# Buttons.net
KiCad netlist of a schematic drawn in EAGLE
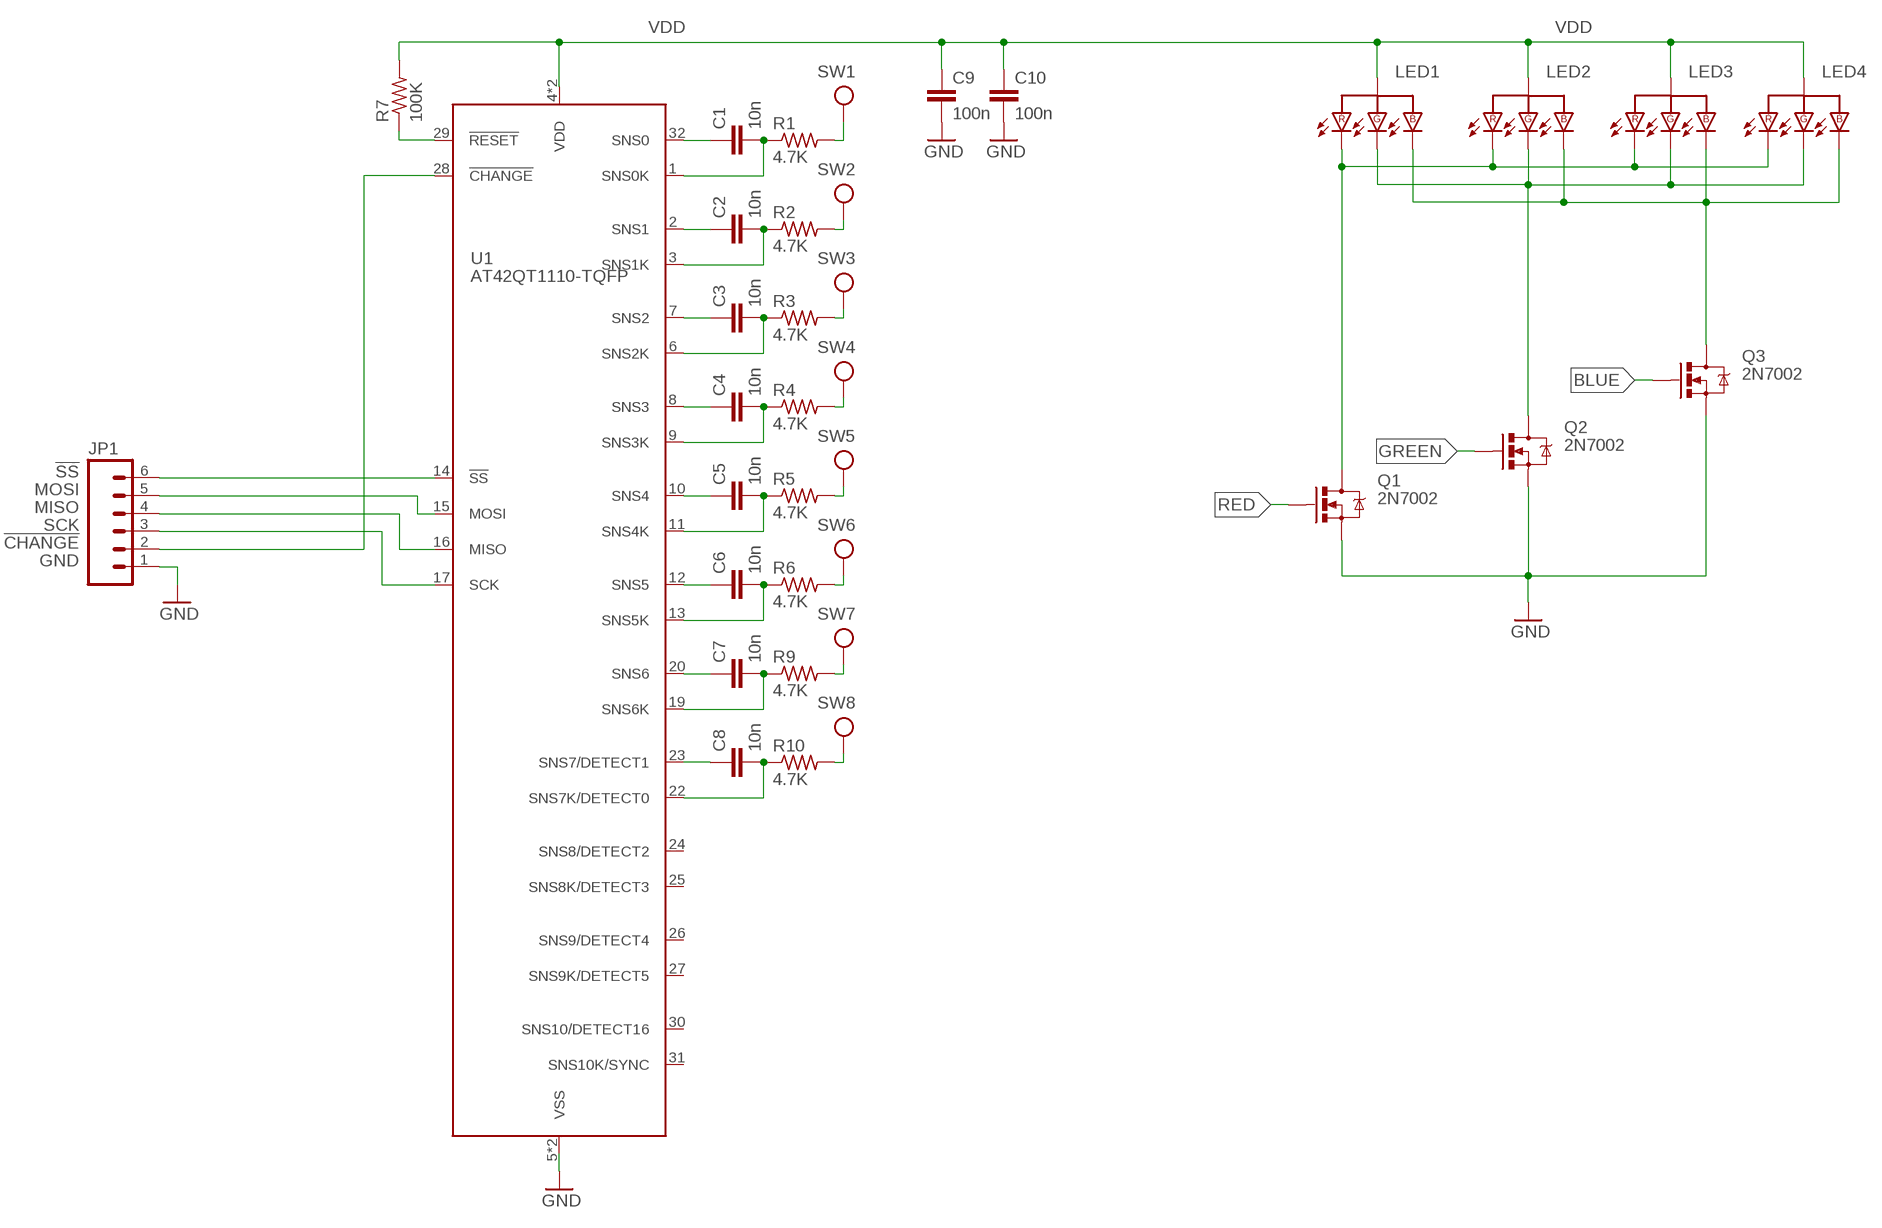
[diagram p0: schematic, sheet 1]

(export (version "E")
  (design (tool "Eeschema 10.0.6"))
  (components
    (comp (ref "C1")
      (value "10n")
      (footprint "eagle-import:C0603")
      (libsource (lib "eagle-import") (part "C-EUC0603"))
    )
    (comp (ref "C2")
      (value "10n")
      (footprint "eagle-import:C0603")
      (libsource (lib "eagle-import") (part "C-EUC0603"))
    )
    (comp (ref "C3")
      (value "10n")
      (footprint "eagle-import:C0603")
      (libsource (lib "eagle-import") (part "C-EUC0603"))
    )
    (comp (ref "C4")
      (value "10n")
      (footprint "eagle-import:C0603")
      (libsource (lib "eagle-import") (part "C-EUC0603"))
    )
    (comp (ref "C5")
      (value "10n")
      (footprint "eagle-import:C0603")
      (libsource (lib "eagle-import") (part "C-EUC0603"))
    )
    (comp (ref "C6")
      (value "10n")
      (footprint "eagle-import:C0603")
      (libsource (lib "eagle-import") (part "C-EUC0603"))
    )
    (comp (ref "C7")
      (value "10n")
      (footprint "eagle-import:C0603")
      (libsource (lib "eagle-import") (part "C-EUC0603"))
    )
    (comp (ref "C8")
      (value "10n")
      (footprint "eagle-import:C0603")
      (libsource (lib "eagle-import") (part "C-EUC0603"))
    )
    (comp (ref "C9")
      (value "100n")
      (footprint "eagle-import:C0603")
      (libsource (lib "eagle-import") (part "C-EUC0603"))
    )
    (comp (ref "C10")
      (value "100n")
      (footprint "eagle-import:C0603")
      (libsource (lib "eagle-import") (part "C-EUC0603"))
    )
    (comp (ref "JP1")
      (value "M06SMD-STRAIGHT")
      (footprint "eagle-import:1X06_SMD_STRAIGHT")
      (libsource (lib "eagle-import") (part "M06SMD-STRAIGHT"))
    )
    (comp (ref "LED1")
      (value "LED_RGB")
      (footprint "eagle-import:PLCC-4")
      (libsource (lib "eagle-import") (part "LED_RGB"))
    )
    (comp (ref "LED2")
      (value "LED_RGB")
      (footprint "eagle-import:PLCC-4")
      (libsource (lib "eagle-import") (part "LED_RGB"))
    )
    (comp (ref "LED3")
      (value "LED_RGB")
      (footprint "eagle-import:PLCC-4")
      (libsource (lib "eagle-import") (part "LED_RGB"))
    )
    (comp (ref "LED4")
      (value "LED_RGB")
      (footprint "eagle-import:PLCC-4")
      (libsource (lib "eagle-import") (part "LED_RGB"))
    )
    (comp (ref "Q1")
      (value "2N7002")
      (footprint "eagle-import:SOT23-3")
      (libsource (lib "eagle-import") (part "MOSFET-NCHANNELSMD"))
    )
    (comp (ref "Q2")
      (value "2N7002")
      (footprint "eagle-import:SOT23-3")
      (libsource (lib "eagle-import") (part "MOSFET-NCHANNELSMD"))
    )
    (comp (ref "Q3")
      (value "2N7002")
      (footprint "eagle-import:SOT23-3")
      (libsource (lib "eagle-import") (part "MOSFET-NCHANNELSMD"))
    )
    (comp (ref "R1")
      (value "4.7K")
      (footprint "eagle-import:R0603")
      (libsource (lib "eagle-import") (part "R-US_R0603"))
    )
    (comp (ref "R2")
      (value "4.7K")
      (footprint "eagle-import:R0603")
      (libsource (lib "eagle-import") (part "R-US_R0603"))
    )
    (comp (ref "R3")
      (value "4.7K")
      (footprint "eagle-import:R0603")
      (libsource (lib "eagle-import") (part "R-US_R0603"))
    )
    (comp (ref "R4")
      (value "4.7K")
      (footprint "eagle-import:R0603")
      (libsource (lib "eagle-import") (part "R-US_R0603"))
    )
    (comp (ref "R5")
      (value "4.7K")
      (footprint "eagle-import:R0603")
      (libsource (lib "eagle-import") (part "R-US_R0603"))
    )
    (comp (ref "R6")
      (value "4.7K")
      (footprint "eagle-import:R0603")
      (libsource (lib "eagle-import") (part "R-US_R0603"))
    )
    (comp (ref "R7")
      (value "100K")
      (footprint "eagle-import:R0603")
      (libsource (lib "eagle-import") (part "R-US_R0603"))
    )
    (comp (ref "R9")
      (value "4.7K")
      (footprint "eagle-import:R0603")
      (libsource (lib "eagle-import") (part "R-US_R0603"))
    )
    (comp (ref "R10")
      (value "4.7K")
      (footprint "eagle-import:R0603")
      (libsource (lib "eagle-import") (part "R-US_R0603"))
    )
    (comp (ref "SW1")
      (value "TOUCH_PAD-CIRCLE-15MM")
      (footprint "eagle-import:TOUCH-CIRCLE-15MM")
      (libsource (lib "eagle-import") (part "TOUCH_PAD-CIRCLE-15MM"))
    )
    (comp (ref "SW2")
      (value "TOUCH_PAD-CIRCLE-15MM")
      (footprint "eagle-import:TOUCH-CIRCLE-15MM")
      (libsource (lib "eagle-import") (part "TOUCH_PAD-CIRCLE-15MM"))
    )
    (comp (ref "SW3")
      (value "TOUCH_PAD-CIRCLE-15MM")
      (footprint "eagle-import:TOUCH-CIRCLE-15MM")
      (libsource (lib "eagle-import") (part "TOUCH_PAD-CIRCLE-15MM"))
    )
    (comp (ref "SW4")
      (value "TOUCH_PAD-CIRCLE-15MM")
      (footprint "eagle-import:TOUCH-CIRCLE-15MM")
      (libsource (lib "eagle-import") (part "TOUCH_PAD-CIRCLE-15MM"))
    )
    (comp (ref "SW5")
      (value "TOUCH_PAD-CIRCLE-15MM")
      (footprint "eagle-import:TOUCH-CIRCLE-15MM")
      (libsource (lib "eagle-import") (part "TOUCH_PAD-CIRCLE-15MM"))
    )
    (comp (ref "SW6")
      (value "TOUCH_PAD-CIRCLE-15MM")
      (footprint "eagle-import:TOUCH-CIRCLE-15MM")
      (libsource (lib "eagle-import") (part "TOUCH_PAD-CIRCLE-15MM"))
    )
    (comp (ref "SW7")
      (value "TOUCH_PAD-CIRCLE-15MM")
      (footprint "eagle-import:TOUCH-CIRCLE-15MM")
      (libsource (lib "eagle-import") (part "TOUCH_PAD-CIRCLE-15MM"))
    )
    (comp (ref "SW8")
      (value "TOUCH_PAD-CIRCLE-15MM")
      (footprint "eagle-import:TOUCH-CIRCLE-15MM")
      (libsource (lib "eagle-import") (part "TOUCH_PAD-CIRCLE-15MM"))
    )
    (comp (ref "U1")
      (value "AT42QT1110-TQFP")
      (footprint "eagle-import:S-PQFP-N32")
      (libsource (lib "eagle-import") (part "AT42QT1110-TQFP"))
    )
  )
  (nets
    (net (code "1") (name "/VDD") (class "Default")
      (node (ref "C10") (pin "1") (pinfunction "1_1") (pintype "passive"))
      (node (ref "C9") (pin "1") (pinfunction "1_1") (pintype "passive"))
      (node (ref "LED1") (pin "2") (pinfunction "A_2") (pintype "passive"))
      (node (ref "LED2") (pin "2") (pinfunction "A_2") (pintype "passive"))
      (node (ref "LED3") (pin "2") (pinfunction "A_2") (pintype "passive"))
      (node (ref "LED4") (pin "2") (pinfunction "A_2") (pintype "passive"))
      (node (ref "R7") (pin "2") (pinfunction "2_2") (pintype "passive"))
      (node (ref "U1") (pin "18") (pinfunction "VDD_18") (pintype "bidirectional"))
      (node (ref "U1") (pin "4") (pinfunction "VDD_4") (pintype "bidirectional"))
    )
    (net (code "2") (name "BLUE") (class "Default")
      (node (ref "Q3") (pin "1") (pinfunction "G_1") (pintype "passive"))
    )
    (net (code "3") (name "GND") (class "Default")
      (node (ref "C10") (pin "2") (pinfunction "2_2") (pintype "passive"))
      (node (ref "C9") (pin "2") (pinfunction "2_2") (pintype "passive"))
      (node (ref "JP1") (pin "1") (pinfunction "1_1") (pintype "passive"))
      (node (ref "Q1") (pin "2") (pinfunction "S_2") (pintype "passive"))
      (node (ref "Q2") (pin "2") (pinfunction "S_2") (pintype "passive"))
      (node (ref "Q3") (pin "2") (pinfunction "S_2") (pintype "passive"))
      (node (ref "U1") (pin "21") (pinfunction "VSS_21") (pintype "bidirectional"))
      (node (ref "U1") (pin "5") (pinfunction "VSS_5") (pintype "bidirectional"))
    )
    (net (code "4") (name "GREEN") (class "Default")
      (node (ref "Q2") (pin "1") (pinfunction "G_1") (pintype "passive"))
    )
    (net (code "5") (name "Net-(LED1-KB)") (class "Default")
      (node (ref "LED1") (pin "3") (pinfunction "KB_3") (pintype "passive"))
      (node (ref "LED2") (pin "3") (pinfunction "KB_3") (pintype "passive"))
      (node (ref "LED3") (pin "3") (pinfunction "KB_3") (pintype "passive"))
      (node (ref "LED4") (pin "3") (pinfunction "KB_3") (pintype "passive"))
      (node (ref "Q3") (pin "3") (pinfunction "D_3") (pintype "passive"))
    )
    (net (code "6") (name "Net-(LED1-KG)") (class "Default")
      (node (ref "LED1") (pin "4") (pinfunction "KG_4") (pintype "passive"))
      (node (ref "LED2") (pin "4") (pinfunction "KG_4") (pintype "passive"))
      (node (ref "LED3") (pin "4") (pinfunction "KG_4") (pintype "passive"))
      (node (ref "LED4") (pin "4") (pinfunction "KG_4") (pintype "passive"))
      (node (ref "Q2") (pin "3") (pinfunction "D_3") (pintype "passive"))
    )
    (net (code "7") (name "Net-(LED1-KR)") (class "Default")
      (node (ref "LED1") (pin "1") (pinfunction "KR_1") (pintype "passive"))
      (node (ref "LED2") (pin "1") (pinfunction "KR_1") (pintype "passive"))
      (node (ref "LED3") (pin "1") (pinfunction "KR_1") (pintype "passive"))
      (node (ref "LED4") (pin "1") (pinfunction "KR_1") (pintype "passive"))
      (node (ref "Q1") (pin "3") (pinfunction "D_3") (pintype "passive"))
    )
    (net (code "8") (name "Net-(R1-Pad2)") (class "Default")
      (node (ref "R1") (pin "2") (pinfunction "2_2") (pintype "passive"))
      (node (ref "SW1") (pin "P$1") (pinfunction "P$1_P$1") (pintype "bidirectional"))
    )
    (net (code "9") (name "Net-(R2-Pad2)") (class "Default")
      (node (ref "R2") (pin "2") (pinfunction "2_2") (pintype "passive"))
      (node (ref "SW2") (pin "P$1") (pinfunction "P$1_P$1") (pintype "bidirectional"))
    )
    (net (code "10") (name "Net-(R3-Pad2)") (class "Default")
      (node (ref "R3") (pin "2") (pinfunction "2_2") (pintype "passive"))
      (node (ref "SW3") (pin "P$1") (pinfunction "P$1_P$1") (pintype "bidirectional"))
    )
    (net (code "11") (name "Net-(R4-Pad2)") (class "Default")
      (node (ref "R4") (pin "2") (pinfunction "2_2") (pintype "passive"))
      (node (ref "SW4") (pin "P$1") (pinfunction "P$1_P$1") (pintype "bidirectional"))
    )
    (net (code "12") (name "Net-(R5-Pad2)") (class "Default")
      (node (ref "R5") (pin "2") (pinfunction "2_2") (pintype "passive"))
      (node (ref "SW5") (pin "P$1") (pinfunction "P$1_P$1") (pintype "bidirectional"))
    )
    (net (code "13") (name "Net-(R6-Pad2)") (class "Default")
      (node (ref "R6") (pin "2") (pinfunction "2_2") (pintype "passive"))
      (node (ref "SW6") (pin "P$1") (pinfunction "P$1_P$1") (pintype "bidirectional"))
    )
    (net (code "14") (name "Net-(R9-Pad2)") (class "Default")
      (node (ref "R9") (pin "2") (pinfunction "2_2") (pintype "passive"))
      (node (ref "SW7") (pin "P$1") (pinfunction "P$1_P$1") (pintype "bidirectional"))
    )
    (net (code "15") (name "Net-(R10-Pad2)") (class "Default")
      (node (ref "R10") (pin "2") (pinfunction "2_2") (pintype "passive"))
      (node (ref "SW8") (pin "P$1") (pinfunction "P$1_P$1") (pintype "bidirectional"))
    )
    (net (code "16") (name "Net-(U1-MISO)") (class "Default")
      (node (ref "JP1") (pin "4") (pinfunction "4_4") (pintype "passive"))
      (node (ref "U1") (pin "16") (pinfunction "MISO_16") (pintype "bidirectional"))
    )
    (net (code "17") (name "Net-(U1-MOSI)") (class "Default")
      (node (ref "JP1") (pin "5") (pinfunction "5_5") (pintype "passive"))
      (node (ref "U1") (pin "15") (pinfunction "MOSI_15") (pintype "bidirectional"))
    )
    (net (code "18") (name "Net-(U1-SCK)") (class "Default")
      (node (ref "JP1") (pin "3") (pinfunction "3_3") (pintype "passive"))
      (node (ref "U1") (pin "17") (pinfunction "SCK_17") (pintype "bidirectional"))
    )
    (net (code "19") (name "Net-(U1-SNS0)") (class "Default")
      (node (ref "C1") (pin "1") (pinfunction "1_1") (pintype "passive"))
      (node (ref "U1") (pin "32") (pinfunction "SNS0_32") (pintype "bidirectional"))
    )
    (net (code "20") (name "Net-(U1-SNS0K)") (class "Default")
      (node (ref "C1") (pin "2") (pinfunction "2_2") (pintype "passive"))
      (node (ref "R1") (pin "1") (pinfunction "1_1") (pintype "passive"))
      (node (ref "U1") (pin "1") (pinfunction "SNS0K_1") (pintype "bidirectional"))
    )
    (net (code "21") (name "Net-(U1-SNS1)") (class "Default")
      (node (ref "C2") (pin "1") (pinfunction "1_1") (pintype "passive"))
      (node (ref "U1") (pin "2") (pinfunction "SNS1_2") (pintype "bidirectional"))
    )
    (net (code "22") (name "Net-(U1-SNS1K)") (class "Default")
      (node (ref "C2") (pin "2") (pinfunction "2_2") (pintype "passive"))
      (node (ref "R2") (pin "1") (pinfunction "1_1") (pintype "passive"))
      (node (ref "U1") (pin "3") (pinfunction "SNS1K_3") (pintype "bidirectional"))
    )
    (net (code "23") (name "Net-(U1-SNS2)") (class "Default")
      (node (ref "C3") (pin "1") (pinfunction "1_1") (pintype "passive"))
      (node (ref "U1") (pin "7") (pinfunction "SNS2_7") (pintype "bidirectional"))
    )
    (net (code "24") (name "Net-(U1-SNS2K)") (class "Default")
      (node (ref "C3") (pin "2") (pinfunction "2_2") (pintype "passive"))
      (node (ref "R3") (pin "1") (pinfunction "1_1") (pintype "passive"))
      (node (ref "U1") (pin "6") (pinfunction "SNS2K_6") (pintype "bidirectional"))
    )
    (net (code "25") (name "Net-(U1-SNS3)") (class "Default")
      (node (ref "C4") (pin "1") (pinfunction "1_1") (pintype "passive"))
      (node (ref "U1") (pin "8") (pinfunction "SNS3_8") (pintype "bidirectional"))
    )
    (net (code "26") (name "Net-(U1-SNS3K)") (class "Default")
      (node (ref "C4") (pin "2") (pinfunction "2_2") (pintype "passive"))
      (node (ref "R4") (pin "1") (pinfunction "1_1") (pintype "passive"))
      (node (ref "U1") (pin "9") (pinfunction "SNS3K_9") (pintype "bidirectional"))
    )
    (net (code "27") (name "Net-(U1-SNS4)") (class "Default")
      (node (ref "C5") (pin "1") (pinfunction "1_1") (pintype "passive"))
      (node (ref "U1") (pin "10") (pinfunction "SNS4_10") (pintype "bidirectional"))
    )
    (net (code "28") (name "Net-(U1-SNS4K)") (class "Default")
      (node (ref "C5") (pin "2") (pinfunction "2_2") (pintype "passive"))
      (node (ref "R5") (pin "1") (pinfunction "1_1") (pintype "passive"))
      (node (ref "U1") (pin "11") (pinfunction "SNS4K_11") (pintype "bidirectional"))
    )
    (net (code "29") (name "Net-(U1-SNS5)") (class "Default")
      (node (ref "C6") (pin "1") (pinfunction "1_1") (pintype "passive"))
      (node (ref "U1") (pin "12") (pinfunction "SNS5_12") (pintype "bidirectional"))
    )
    (net (code "30") (name "Net-(U1-SNS5K)") (class "Default")
      (node (ref "C6") (pin "2") (pinfunction "2_2") (pintype "passive"))
      (node (ref "R6") (pin "1") (pinfunction "1_1") (pintype "passive"))
      (node (ref "U1") (pin "13") (pinfunction "SNS5K_13") (pintype "bidirectional"))
    )
    (net (code "31") (name "Net-(U1-SNS6)") (class "Default")
      (node (ref "C7") (pin "1") (pinfunction "1_1") (pintype "passive"))
      (node (ref "U1") (pin "20") (pinfunction "SNS6_20") (pintype "bidirectional"))
    )
    (net (code "32") (name "Net-(U1-SNS6K)") (class "Default")
      (node (ref "C7") (pin "2") (pinfunction "2_2") (pintype "passive"))
      (node (ref "R9") (pin "1") (pinfunction "1_1") (pintype "passive"))
      (node (ref "U1") (pin "19") (pinfunction "SNS6K_19") (pintype "bidirectional"))
    )
    (net (code "33") (name "Net-(U1-SNS7K{slash}DETECT0)") (class "Default")
      (node (ref "C8") (pin "2") (pinfunction "2_2") (pintype "passive"))
      (node (ref "R10") (pin "1") (pinfunction "1_1") (pintype "passive"))
      (node (ref "U1") (pin "22") (pinfunction "SNS7K/DETECT0_22") (pintype "bidirectional"))
    )
    (net (code "34") (name "Net-(U1-SNS7{slash}DETECT1)") (class "Default")
      (node (ref "C8") (pin "1") (pinfunction "1_1") (pintype "passive"))
      (node (ref "U1") (pin "23") (pinfunction "SNS7/DETECT1_23") (pintype "bidirectional"))
    )
    (net (code "35") (name "Net-(U1-~{CHANGE})") (class "Default")
      (node (ref "JP1") (pin "2") (pinfunction "2_2") (pintype "passive"))
      (node (ref "U1") (pin "28") (pinfunction "~{CHANGE}_28") (pintype "bidirectional"))
    )
    (net (code "36") (name "Net-(U1-~{RESET})") (class "Default")
      (node (ref "R7") (pin "1") (pinfunction "1_1") (pintype "passive"))
      (node (ref "U1") (pin "29") (pinfunction "~{RESET}_29") (pintype "bidirectional"))
    )
    (net (code "37") (name "Net-(U1-~{SS})") (class "Default")
      (node (ref "JP1") (pin "6") (pinfunction "6_6") (pintype "passive"))
      (node (ref "U1") (pin "14") (pinfunction "~{SS}_14") (pintype "bidirectional"))
    )
    (net (code "38") (name "RED") (class "Default")
      (node (ref "Q1") (pin "1") (pinfunction "G_1") (pintype "passive"))
    )
    (net (code "39") (name "unconnected-(U1-SNS8K{slash}DETECT3-Pad25)") (class "Default")
      (node (ref "U1") (pin "25") (pinfunction "SNS8K/DETECT3_25") (pintype "bidirectional"))
    )
    (net (code "40") (name "unconnected-(U1-SNS8{slash}DETECT2-Pad24)") (class "Default")
      (node (ref "U1") (pin "24") (pinfunction "SNS8/DETECT2_24") (pintype "bidirectional"))
    )
    (net (code "41") (name "unconnected-(U1-SNS9K{slash}DETECT5-Pad27)") (class "Default")
      (node (ref "U1") (pin "27") (pinfunction "SNS9K/DETECT5_27") (pintype "bidirectional"))
    )
    (net (code "42") (name "unconnected-(U1-SNS9{slash}DETECT4-Pad26)") (class "Default")
      (node (ref "U1") (pin "26") (pinfunction "SNS9/DETECT4_26") (pintype "bidirectional"))
    )
    (net (code "43") (name "unconnected-(U1-SNS10K{slash}SYNC-Pad31)") (class "Default")
      (node (ref "U1") (pin "31") (pinfunction "SNS10K/SYNC_31") (pintype "bidirectional"))
    )
    (net (code "44") (name "unconnected-(U1-SNS10{slash}DETECT16-Pad30)") (class "Default")
      (node (ref "U1") (pin "30") (pinfunction "SNS10/DETECT16_30") (pintype "bidirectional"))
    )
  )
)
